# main.net
KiCad netlist of a schematic drawn in Altium Designer
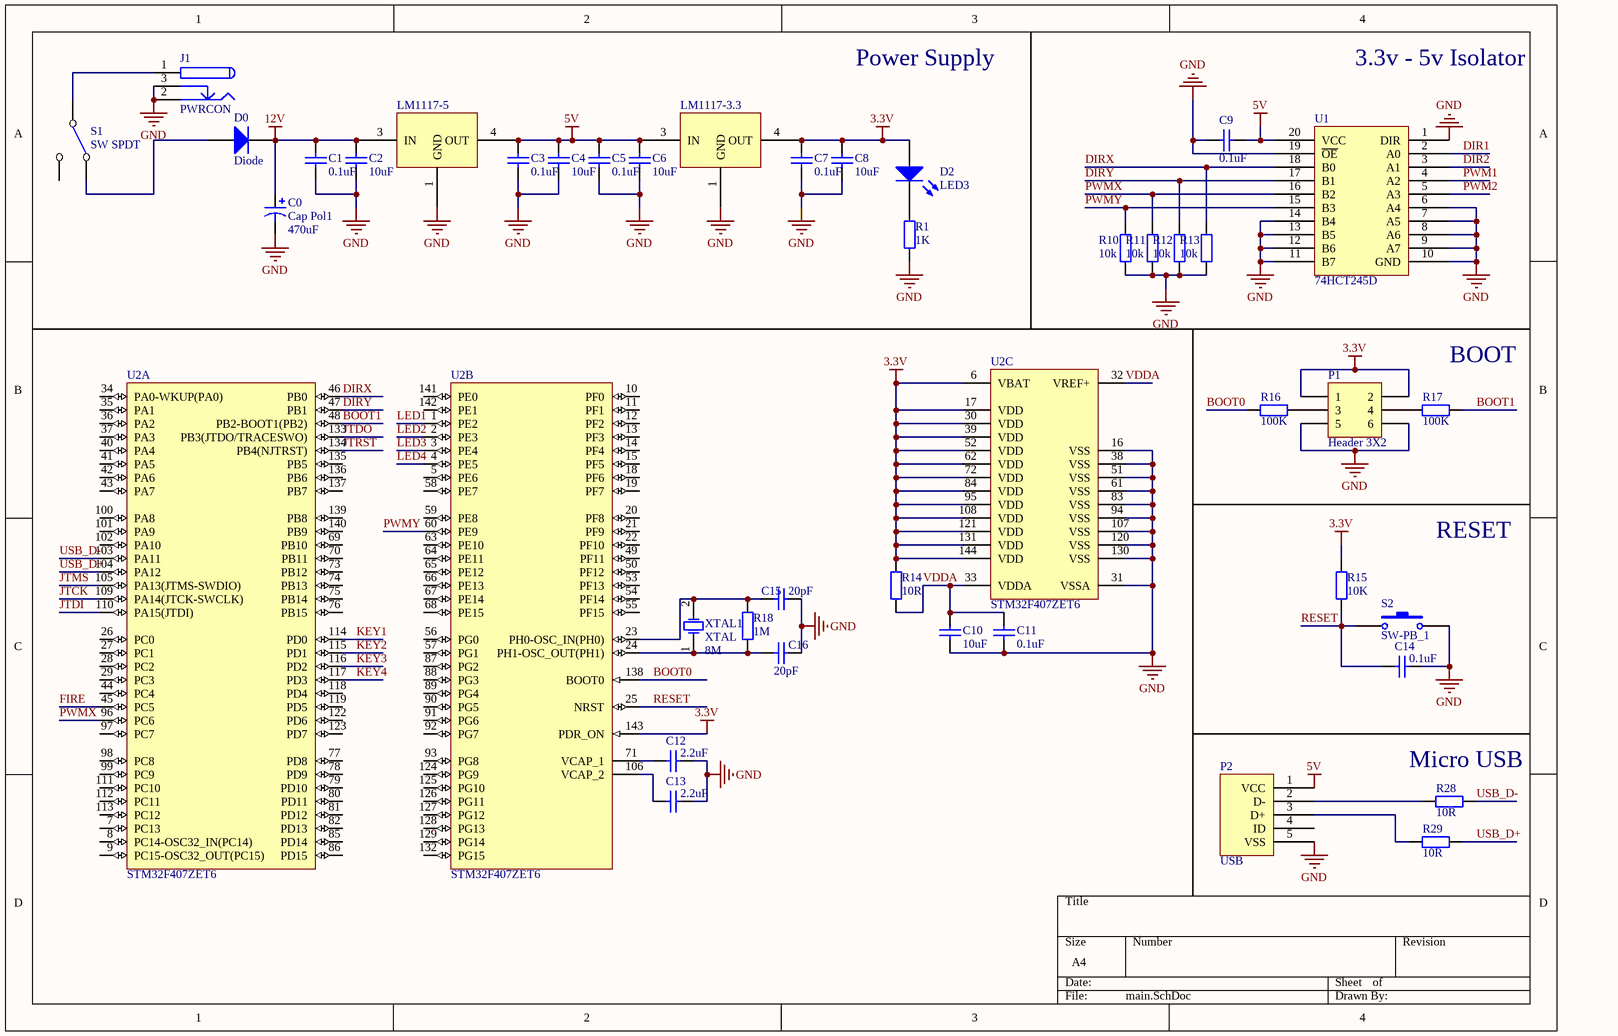
[diagram p0: main.SchDoc]

(export (version "E")
  (design (tool "Eeschema 10.0.6"))
  (components
    (comp (ref "C0")
      (value "Cap Pol1")
      (footprint "CAP-10")
      (description "Polarized Capacitor (Radial)")
      (fields (field (name "ALTIUM_VALUE") "470uF") (field (name "PUBLISHER") "Altium Limited"))
      (libsource (lib "Miscellaneous Devices") (part "Cap Pol1"))
    )
    (comp (ref "C1")
      (value "0.1uF")
      (footprint "C-0603")
      (description "Capacitor (Semiconductor SIM Model)")
      (fields (field (name "Comment") "Cap") (field (name "PUBLISHER") "Altium Limited"))
      (libsource (lib "Miscellaneous Devices") (part "Cap Semi"))
    )
    (comp (ref "C2")
      (value "10uF")
      (footprint "C-0603")
      (description "Capacitor (Semiconductor SIM Model)")
      (fields (field (name "Comment") "Cap") (field (name "PUBLISHER") "Altium Limited"))
      (libsource (lib "Miscellaneous Devices") (part "Cap Semi"))
    )
    (comp (ref "C3")
      (value "0.1uF")
      (footprint "C-0603")
      (description "Capacitor (Semiconductor SIM Model)")
      (fields (field (name "Comment") "Cap") (field (name "PUBLISHER") "Altium Limited"))
      (libsource (lib "Miscellaneous Devices") (part "Cap Semi"))
    )
    (comp (ref "C4")
      (value "10uF")
      (footprint "C-0603")
      (description "Capacitor (Semiconductor SIM Model)")
      (fields (field (name "Comment") "Cap") (field (name "PUBLISHER") "Altium Limited"))
      (libsource (lib "Miscellaneous Devices") (part "Cap Semi"))
    )
    (comp (ref "C5")
      (value "0.1uF")
      (footprint "C-0603")
      (description "Capacitor (Semiconductor SIM Model)")
      (fields (field (name "Comment") "Cap") (field (name "PUBLISHER") "Altium Limited"))
      (libsource (lib "Miscellaneous Devices") (part "Cap Semi"))
    )
    (comp (ref "C6")
      (value "10uF")
      (footprint "C-0603")
      (description "Capacitor (Semiconductor SIM Model)")
      (fields (field (name "Comment") "Cap") (field (name "PUBLISHER") "Altium Limited"))
      (libsource (lib "Miscellaneous Devices") (part "Cap Semi"))
    )
    (comp (ref "C7")
      (value "0.1uF")
      (footprint "C-0603")
      (description "Capacitor (Semiconductor SIM Model)")
      (fields (field (name "Comment") "Cap") (field (name "PUBLISHER") "Altium Limited"))
      (libsource (lib "Miscellaneous Devices") (part "Cap Semi"))
    )
    (comp (ref "C8")
      (value "10uF")
      (footprint "C-0603")
      (description "Capacitor (Semiconductor SIM Model)")
      (fields (field (name "Comment") "Cap") (field (name "PUBLISHER") "Altium Limited"))
      (libsource (lib "Miscellaneous Devices") (part "Cap Semi"))
    )
    (comp (ref "C9")
      (value "0.1uF")
      (footprint "C-0603")
      (description "Capacitor (Semiconductor SIM Model)")
      (fields (field (name "Comment") "Cap") (field (name "PUBLISHER") "Altium Limited"))
      (libsource (lib "Miscellaneous Devices") (part "Cap Semi"))
    )
    (comp (ref "C10")
      (value "10uF")
      (footprint "C-0603")
      (description "Capacitor (Semiconductor SIM Model)")
      (fields (field (name "Comment") "Cap") (field (name "PUBLISHER") "Altium Limited"))
      (libsource (lib "Miscellaneous Devices") (part "Cap Semi"))
    )
    (comp (ref "C11")
      (value "0.1uF")
      (footprint "C-0603")
      (description "Capacitor (Semiconductor SIM Model)")
      (fields (field (name "Comment") "Cap") (field (name "PUBLISHER") "Altium Limited"))
      (libsource (lib "Miscellaneous Devices") (part "Cap Semi"))
    )
    (comp (ref "C12")
      (value "2.2uF")
      (footprint "C-0603")
      (description "Capacitor (Semiconductor SIM Model)")
      (fields (field (name "Comment") "Cap") (field (name "PUBLISHER") "Altium Limited"))
      (libsource (lib "Miscellaneous Devices") (part "Cap Semi"))
    )
    (comp (ref "C13")
      (value "2.2uF")
      (footprint "C-0603")
      (description "Capacitor (Semiconductor SIM Model)")
      (fields (field (name "Comment") "Cap") (field (name "PUBLISHER") "Altium Limited"))
      (libsource (lib "Miscellaneous Devices") (part "Cap Semi"))
    )
    (comp (ref "C14")
      (value "0.1uF")
      (footprint "C-0603")
      (description "Capacitor (Semiconductor SIM Model)")
      (fields (field (name "Comment") "Cap") (field (name "PUBLISHER") "Altium Limited"))
      (libsource (lib "Miscellaneous Devices") (part "Cap Semi"))
    )
    (comp (ref "C15")
      (value "20pF")
      (footprint "C-0603")
      (description "Capacitor (Semiconductor SIM Model)")
      (fields (field (name "Comment") "Cap") (field (name "PUBLISHER") "Altium Limited"))
      (libsource (lib "Miscellaneous Devices") (part "Cap Semi"))
    )
    (comp (ref "C16")
      (value "20pF")
      (footprint "C-0603")
      (description "Capacitor (Semiconductor SIM Model)")
      (fields (field (name "Comment") "Cap") (field (name "PUBLISHER") "Altium Limited"))
      (libsource (lib "Miscellaneous Devices") (part "Cap Semi"))
    )
    (comp (ref "D0")
      (value "Diode")
      (footprint "DIODE-SMA/SMB")
      (description "Default Diode")
      (fields (field (name "PUBLISHER") "Altium Limited"))
      (libsource (lib "Miscellaneous Devices") (part "Diode"))
    )
    (comp (ref "D2")
      (value "LED3")
      (footprint "DIODE-1206")
      (description "Typical BLUE SiC LED")
      (fields (field (name "PUBLISHER") "Altium Limited"))
      (libsource (lib "Miscellaneous Devices") (part "LED3"))
    )
    (comp (ref "J1")
      (value "PWRCON")
      (footprint "DC-005A")
      (description "直流电源端子")
      (fields (field (name "PUBLISHER") "Altium Limited"))
      (libsource (lib "HDR_fszhang") (part "PWRCON"))
    )
    (comp (ref "LM1117-3.3") (value "LM1117") (footprint "lm1117") (libsource (lib "MOS_H") (part "LM1117")))
    (comp (ref "LM1117-5") (value "LM1117") (footprint "lm1117") (libsource (lib "MOS_H") (part "LM1117")))
    (comp (ref "P1")
      (value "Header 3X2")
      (footprint "HDR2X3")
      (description "Header, 3-Pin, Dual row")
      (fields (field (name "PUBLISHER") "Altium Limited"))
      (libsource (lib "Miscellaneous Connectors") (part "Header 3X2"))
    )
    (comp (ref "P2") (value "USB") (footprint "USB_MINI") (libsource (lib "mcu_board") (part "USB")))
    (comp (ref "R1")
      (value "1K")
      (footprint "R-0603")
      (description "Resistor")
      (fields (field (name "Comment") "Res2") (field (name "PUBLISHER") "Altium Limited"))
      (libsource (lib "") (part "Res2_3"))
    )
    (comp (ref "R10")
      (value "10k")
      (footprint "R-0603")
      (description "Resistor")
      (fields (field (name "Comment") "Res2") (field (name "PUBLISHER") "Altium Limited"))
      (libsource (lib "Miscellaneous Devices") (part "Res2"))
    )
    (comp (ref "R11")
      (value "10k")
      (footprint "R-0603")
      (description "Resistor")
      (fields (field (name "Comment") "Res2") (field (name "PUBLISHER") "Altium Limited"))
      (libsource (lib "Miscellaneous Devices") (part "Res2"))
    )
    (comp (ref "R12")
      (value "10k")
      (footprint "R-0603")
      (description "Resistor")
      (fields (field (name "Comment") "Res2") (field (name "PUBLISHER") "Altium Limited"))
      (libsource (lib "Miscellaneous Devices") (part "Res2"))
    )
    (comp (ref "R13")
      (value "10k")
      (footprint "R-0603")
      (description "Resistor")
      (fields (field (name "Comment") "Res2") (field (name "PUBLISHER") "Altium Limited"))
      (libsource (lib "Miscellaneous Devices") (part "Res2"))
    )
    (comp (ref "R14")
      (value "10R")
      (footprint "R-0603")
      (description "Resistor")
      (fields (field (name "Comment") "Res2") (field (name "PUBLISHER") "Altium Limited"))
      (libsource (lib "") (part "Res2_2"))
    )
    (comp (ref "R15")
      (value "10K")
      (footprint "R-0603")
      (description "Resistor")
      (fields (field (name "Comment") "Res2") (field (name "PUBLISHER") "Altium Limited"))
      (libsource (lib "") (part "Res2_2"))
    )
    (comp (ref "R16")
      (value "100K")
      (footprint "R-0603")
      (description "Resistor")
      (fields (field (name "Comment") "Res2") (field (name "PUBLISHER") "Altium Limited"))
      (libsource (lib "") (part "Res2_1"))
    )
    (comp (ref "R17")
      (value "100K")
      (footprint "R-0603")
      (description "Resistor")
      (fields (field (name "Comment") "Res2") (field (name "PUBLISHER") "Altium Limited"))
      (libsource (lib "") (part "Res2_1"))
    )
    (comp (ref "R18")
      (value "1M")
      (footprint "R-0603")
      (description "Resistor")
      (fields (field (name "Comment") "Res2") (field (name "PUBLISHER") "Altium Limited"))
      (libsource (lib "") (part "Res2_2"))
    )
    (comp (ref "R28")
      (value "10R")
      (footprint "R-0603")
      (description "Resistor")
      (fields (field (name "Comment") "Res2") (field (name "PUBLISHER") "Altium Limited"))
      (libsource (lib "") (part "Res2_1"))
    )
    (comp (ref "R29")
      (value "10R")
      (footprint "R-0603")
      (description "Resistor")
      (fields (field (name "Comment") "Res2") (field (name "PUBLISHER") "Altium Limited"))
      (libsource (lib "") (part "Res2_1"))
    )
    (comp (ref "S1") (value "SW SPDT") (footprint "SW3P") (libsource (lib "MOS_H") (part "SW SPDT")))
    (comp (ref "S2")
      (value "SW-PB_1")
      (footprint "SW-2-6*3")
      (description "Switch")
      (fields (field (name "PUBLISHER") "Altium Limited"))
      (libsource (lib "mcu_board") (part "SW-PB_1"))
    )
    (comp (ref "U1") (value "74HCT245D") (footprint "TSSOP20") (libsource (lib "MOS_H") (part "74lvc245")))
    (comp (ref "U2")
      (value "STM32F407ZET6")
      (footprint "STM-LQFP144_M")
      (fields (field (name "MANUFACTURER") "STMicroelectronics"))
      (libsource (lib "STMicroelectronics STM32 F4") (part "STM32F407ZET6"))
    )
    (comp (ref "XTAL1")
      (value "XTAL")
      (footprint "XTAL-QC49/SMD")
      (fields (field (name "FREQUENCE") "8M"))
      (libsource (lib "mcu_board") (part "XTAL"))
    )
  )
  (nets
    (net (code "1") (name "/BOOT0") (class "Default")
      (node (ref "R16") (pin "2") (pinfunction "2_2") (pintype "passive"))
      (node (ref "U2") (pin "138") (pinfunction "BOOT0_138") (pintype "input"))
    )
    (net (code "2") (name "/BOOT1") (class "Default")
      (node (ref "R17") (pin "1") (pinfunction "1_1") (pintype "passive"))
      (node (ref "U2") (pin "48") (pinfunction "PB2-BOOT1(PB2)_48") (pintype "bidirectional"))
    )
    (net (code "3") (name "/DIR1") (class "Default")
      (node (ref "U1") (pin "2") (pinfunction "A0_2") (pintype "passive"))
    )
    (net (code "4") (name "/DIR2") (class "Default")
      (node (ref "U1") (pin "3") (pinfunction "A1_3") (pintype "passive"))
    )
    (net (code "5") (name "/DIRX") (class "Default")
      (node (ref "R13") (pin "1") (pinfunction "1_1") (pintype "passive"))
      (node (ref "U1") (pin "18") (pinfunction "B0_18") (pintype "passive"))
      (node (ref "U2") (pin "46") (pinfunction "PB0_46") (pintype "bidirectional"))
    )
    (net (code "6") (name "/DIRY") (class "Default")
      (node (ref "R12") (pin "1") (pinfunction "1_1") (pintype "passive"))
      (node (ref "U1") (pin "17") (pinfunction "B1_17") (pintype "passive"))
      (node (ref "U2") (pin "47") (pinfunction "PB1_47") (pintype "bidirectional"))
    )
    (net (code "7") (name "/FIRE") (class "Default")
      (node (ref "U2") (pin "45") (pinfunction "PC5_45") (pintype "bidirectional"))
    )
    (net (code "8") (name "/JTCK") (class "Default")
      (node (ref "U2") (pin "109") (pinfunction "PA14(JTCK-SWCLK)_109") (pintype "bidirectional"))
    )
    (net (code "9") (name "/JTDI") (class "Default")
      (node (ref "U2") (pin "110") (pinfunction "PA15(JTDI)_110") (pintype "bidirectional"))
    )
    (net (code "10") (name "/JTDO") (class "Default")
      (node (ref "U2") (pin "133") (pinfunction "PB3(JTDO/TRACESWO)_133") (pintype "bidirectional"))
    )
    (net (code "11") (name "/JTMS") (class "Default")
      (node (ref "U2") (pin "105") (pinfunction "PA13(JTMS-SWDIO)_105") (pintype "bidirectional"))
    )
    (net (code "12") (name "/JTRST") (class "Default")
      (node (ref "U2") (pin "134") (pinfunction "PB4(NJTRST)_134") (pintype "bidirectional"))
    )
    (net (code "13") (name "/KEY1") (class "Default")
      (node (ref "U2") (pin "114") (pinfunction "PD0_114") (pintype "bidirectional"))
    )
    (net (code "14") (name "/KEY2") (class "Default")
      (node (ref "U2") (pin "115") (pinfunction "PD1_115") (pintype "bidirectional"))
    )
    (net (code "15") (name "/KEY3") (class "Default")
      (node (ref "U2") (pin "116") (pinfunction "PD2_116") (pintype "bidirectional"))
    )
    (net (code "16") (name "/KEY4") (class "Default")
      (node (ref "U2") (pin "117") (pinfunction "PD3_117") (pintype "bidirectional"))
    )
    (net (code "17") (name "/LED1") (class "Default")
      (node (ref "U2") (pin "1") (pinfunction "PE2_1") (pintype "bidirectional"))
    )
    (net (code "18") (name "/LED2") (class "Default")
      (node (ref "U2") (pin "2") (pinfunction "PE3_2") (pintype "bidirectional"))
    )
    (net (code "19") (name "/LED3") (class "Default")
      (node (ref "U2") (pin "3") (pinfunction "PE4_3") (pintype "bidirectional"))
    )
    (net (code "20") (name "/LED4") (class "Default")
      (node (ref "U2") (pin "4") (pinfunction "PE5_4") (pintype "bidirectional"))
    )
    (net (code "21") (name "/PWM1") (class "Default")
      (node (ref "U1") (pin "4") (pinfunction "A2_4") (pintype "passive"))
    )
    (net (code "22") (name "/PWM2") (class "Default")
      (node (ref "U1") (pin "5") (pinfunction "A3_5") (pintype "passive"))
    )
    (net (code "23") (name "/PWMX") (class "Default")
      (node (ref "R11") (pin "1") (pinfunction "1_1") (pintype "passive"))
      (node (ref "U1") (pin "16") (pinfunction "B2_16") (pintype "passive"))
      (node (ref "U2") (pin "96") (pinfunction "PC6_96") (pintype "bidirectional"))
    )
    (net (code "24") (name "/PWMY") (class "Default")
      (node (ref "R10") (pin "1") (pinfunction "1_1") (pintype "passive"))
      (node (ref "U1") (pin "15") (pinfunction "B3_15") (pintype "passive"))
      (node (ref "U2") (pin "60") (pinfunction "PE9_60") (pintype "bidirectional"))
    )
    (net (code "25") (name "/RESET") (class "Default")
      (node (ref "C14") (pin "2") (pinfunction "2_2") (pintype "passive"))
      (node (ref "R15") (pin "1") (pinfunction "1_1") (pintype "passive"))
      (node (ref "S2") (pin "1") (pinfunction "1_1") (pintype "passive"))
      (node (ref "U2") (pin "25") (pinfunction "NRST_25") (pintype "bidirectional"))
    )
    (net (code "26") (name "/USB_D+") (class "Default")
      (node (ref "R29") (pin "1") (pinfunction "1_1") (pintype "passive"))
      (node (ref "U2") (pin "104") (pinfunction "PA12_104") (pintype "bidirectional"))
    )
    (net (code "27") (name "/USB_D-") (class "Default")
      (node (ref "R28") (pin "1") (pinfunction "1_1") (pintype "passive"))
      (node (ref "U2") (pin "103") (pinfunction "PA11_103") (pintype "bidirectional"))
    )
    (net (code "28") (name "/VDDA") (class "Default")
      (node (ref "C10") (pin "2") (pinfunction "2_2") (pintype "passive"))
      (node (ref "C11") (pin "2") (pinfunction "2_2") (pintype "passive"))
      (node (ref "R14") (pin "1") (pinfunction "1_1") (pintype "passive"))
      (node (ref "U2") (pin "32") (pinfunction "VREF+_32") (pintype "power_in"))
      (node (ref "U2") (pin "33") (pinfunction "VDDA_33") (pintype "power_in"))
    )
    (net (code "29") (name "3.3V") (class "Default")
      (node (ref "C7") (pin "2") (pinfunction "2_2") (pintype "passive"))
      (node (ref "C8") (pin "2") (pinfunction "2_2") (pintype "passive"))
      (node (ref "D2") (pin "1") (pinfunction "A_1") (pintype "passive"))
      (node (ref "LM1117-3.3") (pin "4") (pinfunction "OUT_4") (pintype "passive"))
      (node (ref "P1") (pin "1") (pinfunction "1_1") (pintype "passive"))
      (node (ref "P1") (pin "2") (pinfunction "2_2") (pintype "passive"))
      (node (ref "R14") (pin "2") (pinfunction "2_2") (pintype "passive"))
      (node (ref "R15") (pin "2") (pinfunction "2_2") (pintype "passive"))
      (node (ref "U2") (pin "108") (pinfunction "VDD_108") (pintype "power_in"))
      (node (ref "U2") (pin "121") (pinfunction "VDD_121") (pintype "power_in"))
      (node (ref "U2") (pin "131") (pinfunction "VDD_131") (pintype "power_in"))
      (node (ref "U2") (pin "143") (pinfunction "PDR_ON_143") (pintype "input"))
      (node (ref "U2") (pin "144") (pinfunction "VDD_144") (pintype "power_in"))
      (node (ref "U2") (pin "17") (pinfunction "VDD_17") (pintype "power_in"))
      (node (ref "U2") (pin "30") (pinfunction "VDD_30") (pintype "power_in"))
      (node (ref "U2") (pin "39") (pinfunction "VDD_39") (pintype "power_in"))
      (node (ref "U2") (pin "52") (pinfunction "VDD_52") (pintype "power_in"))
      (node (ref "U2") (pin "6") (pinfunction "VBAT_6") (pintype "power_in"))
      (node (ref "U2") (pin "62") (pinfunction "VDD_62") (pintype "power_in"))
      (node (ref "U2") (pin "72") (pinfunction "VDD_72") (pintype "power_in"))
      (node (ref "U2") (pin "84") (pinfunction "VDD_84") (pintype "power_in"))
      (node (ref "U2") (pin "95") (pinfunction "VDD_95") (pintype "power_in"))
    )
    (net (code "30") (name "5V") (class "Default")
      (node (ref "C3") (pin "2") (pinfunction "2_2") (pintype "passive"))
      (node (ref "C4") (pin "2") (pinfunction "2_2") (pintype "passive"))
      (node (ref "C5") (pin "2") (pinfunction "2_2") (pintype "passive"))
      (node (ref "C6") (pin "2") (pinfunction "2_2") (pintype "passive"))
      (node (ref "C9") (pin "1") (pinfunction "1_1") (pintype "passive"))
      (node (ref "LM1117-3.3") (pin "3") (pinfunction "IN_3") (pintype "passive"))
      (node (ref "LM1117-5") (pin "4") (pinfunction "OUT_4") (pintype "passive"))
      (node (ref "P2") (pin "1") (pinfunction "VCC_1") (pintype "passive"))
      (node (ref "U1") (pin "20") (pinfunction "VCC_20") (pintype "passive"))
    )
    (net (code "31") (name "12V") (class "Default")
      (node (ref "C0") (pin "1") (pinfunction "1_1") (pintype "passive"))
      (node (ref "C1") (pin "2") (pinfunction "2_2") (pintype "passive"))
      (node (ref "C2") (pin "2") (pinfunction "2_2") (pintype "passive"))
      (node (ref "D0") (pin "2") (pinfunction "K_2") (pintype "passive"))
      (node (ref "LM1117-5") (pin "3") (pinfunction "IN_3") (pintype "passive"))
    )
    (net (code "32") (name "GND") (class "Default")
      (node (ref "C0") (pin "2") (pinfunction "2_2") (pintype "passive"))
      (node (ref "C1") (pin "1") (pinfunction "1_1") (pintype "passive"))
      (node (ref "C10") (pin "1") (pinfunction "1_1") (pintype "passive"))
      (node (ref "C11") (pin "1") (pinfunction "1_1") (pintype "passive"))
      (node (ref "C12") (pin "1") (pinfunction "1_1") (pintype "passive"))
      (node (ref "C13") (pin "1") (pinfunction "1_1") (pintype "passive"))
      (node (ref "C14") (pin "1") (pinfunction "1_1") (pintype "passive"))
      (node (ref "C15") (pin "2") (pinfunction "2_2") (pintype "passive"))
      (node (ref "C16") (pin "2") (pinfunction "2_2") (pintype "passive"))
      (node (ref "C2") (pin "1") (pinfunction "1_1") (pintype "passive"))
      (node (ref "C3") (pin "1") (pinfunction "1_1") (pintype "passive"))
      (node (ref "C4") (pin "1") (pinfunction "1_1") (pintype "passive"))
      (node (ref "C5") (pin "1") (pinfunction "1_1") (pintype "passive"))
      (node (ref "C6") (pin "1") (pinfunction "1_1") (pintype "passive"))
      (node (ref "C7") (pin "1") (pinfunction "1_1") (pintype "passive"))
      (node (ref "C8") (pin "1") (pinfunction "1_1") (pintype "passive"))
      (node (ref "C9") (pin "2") (pinfunction "2_2") (pintype "passive"))
      (node (ref "J1") (pin "2") (pinfunction "2_2") (pintype "power_in"))
      (node (ref "J1") (pin "3") (pinfunction "3_3") (pintype "power_in"))
      (node (ref "LM1117-3.3") (pin "1") (pinfunction "GND_1") (pintype "passive"))
      (node (ref "LM1117-5") (pin "1") (pinfunction "GND_1") (pintype "passive"))
      (node (ref "P1") (pin "5") (pinfunction "5_5") (pintype "passive"))
      (node (ref "P1") (pin "6") (pinfunction "6_6") (pintype "passive"))
      (node (ref "P2") (pin "5") (pinfunction "VSS_5") (pintype "passive"))
      (node (ref "R1") (pin "1") (pinfunction "1_1") (pintype "passive"))
      (node (ref "R10") (pin "2") (pinfunction "2_2") (pintype "passive"))
      (node (ref "R11") (pin "2") (pinfunction "2_2") (pintype "passive"))
      (node (ref "R12") (pin "2") (pinfunction "2_2") (pintype "passive"))
      (node (ref "R13") (pin "2") (pinfunction "2_2") (pintype "passive"))
      (node (ref "S2") (pin "2") (pinfunction "2_2") (pintype "passive"))
      (node (ref "U1") (pin "1") (pinfunction "DIR_1") (pintype "passive"))
      (node (ref "U1") (pin "10") (pinfunction "GND_10") (pintype "passive"))
      (node (ref "U1") (pin "11") (pinfunction "B7_11") (pintype "passive"))
      (node (ref "U1") (pin "12") (pinfunction "B6_12") (pintype "passive"))
      (node (ref "U1") (pin "13") (pinfunction "B5_13") (pintype "passive"))
      (node (ref "U1") (pin "14") (pinfunction "B4_14") (pintype "passive"))
      (node (ref "U1") (pin "19") (pinfunction "~{OE}_19") (pintype "passive"))
      (node (ref "U1") (pin "6") (pinfunction "A4_6") (pintype "passive"))
      (node (ref "U1") (pin "7") (pinfunction "A5_7") (pintype "passive"))
      (node (ref "U1") (pin "8") (pinfunction "A6_8") (pintype "passive"))
      (node (ref "U1") (pin "9") (pinfunction "A7_9") (pintype "passive"))
      (node (ref "U2") (pin "107") (pinfunction "VSS_107") (pintype "power_in"))
      (node (ref "U2") (pin "120") (pinfunction "VSS_120") (pintype "power_in"))
      (node (ref "U2") (pin "130") (pinfunction "VSS_130") (pintype "power_in"))
      (node (ref "U2") (pin "16") (pinfunction "VSS_16") (pintype "power_in"))
      (node (ref "U2") (pin "31") (pinfunction "VSSA_31") (pintype "power_in"))
      (node (ref "U2") (pin "38") (pinfunction "VSS_38") (pintype "power_in"))
      (node (ref "U2") (pin "51") (pinfunction "VSS_51") (pintype "power_in"))
      (node (ref "U2") (pin "61") (pinfunction "VSS_61") (pintype "power_in"))
      (node (ref "U2") (pin "83") (pinfunction "VSS_83") (pintype "power_in"))
      (node (ref "U2") (pin "94") (pinfunction "VSS_94") (pintype "power_in"))
    )
    (net (code "33") (name "Net-(D0-A)") (class "Default")
      (node (ref "D0") (pin "1") (pinfunction "A_1") (pintype "passive"))
      (node (ref "S1") (pin "2") (pinfunction "NC_2") (pintype "passive"))
    )
    (net (code "34") (name "Net-(D2-K)") (class "Default")
      (node (ref "D2") (pin "2") (pinfunction "K_2") (pintype "passive"))
      (node (ref "R1") (pin "2") (pinfunction "2_2") (pintype "passive"))
    )
    (net (code "35") (name "Net-(P1-Pad3)") (class "Default")
      (node (ref "P1") (pin "3") (pinfunction "3_3") (pintype "passive"))
      (node (ref "R16") (pin "1") (pinfunction "1_1") (pintype "passive"))
    )
    (net (code "36") (name "Net-(P1-Pad4)") (class "Default")
      (node (ref "P1") (pin "4") (pinfunction "4_4") (pintype "passive"))
      (node (ref "R17") (pin "2") (pinfunction "2_2") (pintype "passive"))
    )
    (net (code "37") (name "Net-(P2-D+)") (class "Default")
      (node (ref "P2") (pin "3") (pinfunction "D+_3") (pintype "passive"))
      (node (ref "R29") (pin "2") (pinfunction "2_2") (pintype "passive"))
    )
    (net (code "38") (name "Net-(P2-D-)") (class "Default")
      (node (ref "P2") (pin "2") (pinfunction "D-_2") (pintype "passive"))
      (node (ref "R28") (pin "2") (pinfunction "2_2") (pintype "passive"))
    )
    (net (code "39") (name "Net-(S1-COMMON)") (class "Default")
      (node (ref "J1") (pin "1") (pinfunction "1_1") (pintype "power_in"))
      (node (ref "S1") (pin "1") (pinfunction "COMMON_1") (pintype "passive"))
    )
    (net (code "40") (name "Net-(U2B-PH0-OSC_IN(PH0))") (class "Default")
      (node (ref "C15") (pin "1") (pinfunction "1_1") (pintype "passive"))
      (node (ref "R18") (pin "2") (pinfunction "2_2") (pintype "passive"))
      (node (ref "U2") (pin "23") (pinfunction "PH0-OSC_IN(PH0)_23") (pintype "bidirectional"))
      (node (ref "XTAL1") (pin "2") (pinfunction "2_2") (pintype "passive"))
    )
    (net (code "41") (name "Net-(U2B-PH1-OSC_OUT(PH1))") (class "Default")
      (node (ref "C16") (pin "1") (pinfunction "1_1") (pintype "passive"))
      (node (ref "R18") (pin "1") (pinfunction "1_1") (pintype "passive"))
      (node (ref "U2") (pin "24") (pinfunction "PH1-OSC_OUT(PH1)_24") (pintype "bidirectional"))
      (node (ref "XTAL1") (pin "1") (pinfunction "1_1") (pintype "passive"))
    )
    (net (code "42") (name "Net-(U2B-VCAP_1)") (class "Default")
      (node (ref "C12") (pin "2") (pinfunction "2_2") (pintype "passive"))
      (node (ref "U2") (pin "71") (pinfunction "VCAP_1_71") (pintype "power_in"))
    )
    (net (code "43") (name "Net-(U2B-VCAP_2)") (class "Default")
      (node (ref "C13") (pin "2") (pinfunction "2_2") (pintype "passive"))
      (node (ref "U2") (pin "106") (pinfunction "VCAP_2_106") (pintype "power_in"))
    )
    (net (code "44") (name "unconnected-(P2-ID-Pad4)") (class "Default")
      (node (ref "P2") (pin "4") (pinfunction "ID_4") (pintype "passive"))
    )
    (net (code "45") (name "unconnected-(S1-NO-Pad3)") (class "Default")
      (node (ref "S1") (pin "3") (pinfunction "NO_3") (pintype "passive"))
    )
    (net (code "46") (name "unconnected-(U2A-PA0-WKUP(PA0)-Pad34)") (class "Default")
      (node (ref "U2") (pin "34") (pinfunction "PA0-WKUP(PA0)_34") (pintype "bidirectional"))
    )
    (net (code "47") (name "unconnected-(U2A-PA1-Pad35)") (class "Default")
      (node (ref "U2") (pin "35") (pinfunction "PA1_35") (pintype "bidirectional"))
    )
    (net (code "48") (name "unconnected-(U2A-PA2-Pad36)") (class "Default")
      (node (ref "U2") (pin "36") (pinfunction "PA2_36") (pintype "bidirectional"))
    )
    (net (code "49") (name "unconnected-(U2A-PA3-Pad37)") (class "Default")
      (node (ref "U2") (pin "37") (pinfunction "PA3_37") (pintype "bidirectional"))
    )
    (net (code "50") (name "unconnected-(U2A-PA4-Pad40)") (class "Default")
      (node (ref "U2") (pin "40") (pinfunction "PA4_40") (pintype "bidirectional"))
    )
    (net (code "51") (name "unconnected-(U2A-PA5-Pad41)") (class "Default")
      (node (ref "U2") (pin "41") (pinfunction "PA5_41") (pintype "bidirectional"))
    )
    (net (code "52") (name "unconnected-(U2A-PA6-Pad42)") (class "Default")
      (node (ref "U2") (pin "42") (pinfunction "PA6_42") (pintype "bidirectional"))
    )
    (net (code "53") (name "unconnected-(U2A-PA7-Pad43)") (class "Default")
      (node (ref "U2") (pin "43") (pinfunction "PA7_43") (pintype "bidirectional"))
    )
    (net (code "54") (name "unconnected-(U2A-PA8-Pad100)") (class "Default")
      (node (ref "U2") (pin "100") (pinfunction "PA8_100") (pintype "bidirectional"))
    )
    (net (code "55") (name "unconnected-(U2A-PA9-Pad101)") (class "Default")
      (node (ref "U2") (pin "101") (pinfunction "PA9_101") (pintype "bidirectional"))
    )
    (net (code "56") (name "unconnected-(U2A-PA10-Pad102)") (class "Default")
      (node (ref "U2") (pin "102") (pinfunction "PA10_102") (pintype "bidirectional"))
    )
    (net (code "57") (name "unconnected-(U2A-PB5-Pad135)") (class "Default")
      (node (ref "U2") (pin "135") (pinfunction "PB5_135") (pintype "bidirectional"))
    )
    (net (code "58") (name "unconnected-(U2A-PB6-Pad136)") (class "Default")
      (node (ref "U2") (pin "136") (pinfunction "PB6_136") (pintype "bidirectional"))
    )
    (net (code "59") (name "unconnected-(U2A-PB7-Pad137)") (class "Default")
      (node (ref "U2") (pin "137") (pinfunction "PB7_137") (pintype "bidirectional"))
    )
    (net (code "60") (name "unconnected-(U2A-PB8-Pad139)") (class "Default")
      (node (ref "U2") (pin "139") (pinfunction "PB8_139") (pintype "bidirectional"))
    )
    (net (code "61") (name "unconnected-(U2A-PB9-Pad140)") (class "Default")
      (node (ref "U2") (pin "140") (pinfunction "PB9_140") (pintype "bidirectional"))
    )
    (net (code "62") (name "unconnected-(U2A-PB10-Pad69)") (class "Default")
      (node (ref "U2") (pin "69") (pinfunction "PB10_69") (pintype "bidirectional"))
    )
    (net (code "63") (name "unconnected-(U2A-PB11-Pad70)") (class "Default")
      (node (ref "U2") (pin "70") (pinfunction "PB11_70") (pintype "bidirectional"))
    )
    (net (code "64") (name "unconnected-(U2A-PB12-Pad73)") (class "Default")
      (node (ref "U2") (pin "73") (pinfunction "PB12_73") (pintype "bidirectional"))
    )
    (net (code "65") (name "unconnected-(U2A-PB13-Pad74)") (class "Default")
      (node (ref "U2") (pin "74") (pinfunction "PB13_74") (pintype "bidirectional"))
    )
    (net (code "66") (name "unconnected-(U2A-PB14-Pad75)") (class "Default")
      (node (ref "U2") (pin "75") (pinfunction "PB14_75") (pintype "bidirectional"))
    )
    (net (code "67") (name "unconnected-(U2A-PB15-Pad76)") (class "Default")
      (node (ref "U2") (pin "76") (pinfunction "PB15_76") (pintype "bidirectional"))
    )
    (net (code "68") (name "unconnected-(U2A-PC0-Pad26)") (class "Default")
      (node (ref "U2") (pin "26") (pinfunction "PC0_26") (pintype "bidirectional"))
    )
    (net (code "69") (name "unconnected-(U2A-PC1-Pad27)") (class "Default")
      (node (ref "U2") (pin "27") (pinfunction "PC1_27") (pintype "bidirectional"))
    )
    (net (code "70") (name "unconnected-(U2A-PC2-Pad28)") (class "Default")
      (node (ref "U2") (pin "28") (pinfunction "PC2_28") (pintype "bidirectional"))
    )
    (net (code "71") (name "unconnected-(U2A-PC3-Pad29)") (class "Default")
      (node (ref "U2") (pin "29") (pinfunction "PC3_29") (pintype "bidirectional"))
    )
    (net (code "72") (name "unconnected-(U2A-PC4-Pad44)") (class "Default")
      (node (ref "U2") (pin "44") (pinfunction "PC4_44") (pintype "bidirectional"))
    )
    (net (code "73") (name "unconnected-(U2A-PC7-Pad97)") (class "Default")
      (node (ref "U2") (pin "97") (pinfunction "PC7_97") (pintype "bidirectional"))
    )
    (net (code "74") (name "unconnected-(U2A-PC8-Pad98)") (class "Default")
      (node (ref "U2") (pin "98") (pinfunction "PC8_98") (pintype "bidirectional"))
    )
    (net (code "75") (name "unconnected-(U2A-PC9-Pad99)") (class "Default")
      (node (ref "U2") (pin "99") (pinfunction "PC9_99") (pintype "bidirectional"))
    )
    (net (code "76") (name "unconnected-(U2A-PC10-Pad111)") (class "Default")
      (node (ref "U2") (pin "111") (pinfunction "PC10_111") (pintype "bidirectional"))
    )
    (net (code "77") (name "unconnected-(U2A-PC11-Pad112)") (class "Default")
      (node (ref "U2") (pin "112") (pinfunction "PC11_112") (pintype "bidirectional"))
    )
    (net (code "78") (name "unconnected-(U2A-PC12-Pad113)") (class "Default")
      (node (ref "U2") (pin "113") (pinfunction "PC12_113") (pintype "bidirectional"))
    )
    (net (code "79") (name "unconnected-(U2A-PC13-Pad7)") (class "Default")
      (node (ref "U2") (pin "7") (pinfunction "PC13_7") (pintype "bidirectional"))
    )
    (net (code "80") (name "unconnected-(U2A-PC14-OSC32_IN(PC14)-Pad8)") (class "Default")
      (node (ref "U2") (pin "8") (pinfunction "PC14-OSC32_IN(PC14)_8") (pintype "bidirectional"))
    )
    (net (code "81") (name "unconnected-(U2A-PC15-OSC32_OUT(PC15)-Pad9)") (class "Default")
      (node (ref "U2") (pin "9") (pinfunction "PC15-OSC32_OUT(PC15)_9") (pintype "bidirectional"))
    )
    (net (code "82") (name "unconnected-(U2A-PD4-Pad118)") (class "Default")
      (node (ref "U2") (pin "118") (pinfunction "PD4_118") (pintype "bidirectional"))
    )
    (net (code "83") (name "unconnected-(U2A-PD5-Pad119)") (class "Default")
      (node (ref "U2") (pin "119") (pinfunction "PD5_119") (pintype "bidirectional"))
    )
    (net (code "84") (name "unconnected-(U2A-PD6-Pad122)") (class "Default")
      (node (ref "U2") (pin "122") (pinfunction "PD6_122") (pintype "bidirectional"))
    )
    (net (code "85") (name "unconnected-(U2A-PD7-Pad123)") (class "Default")
      (node (ref "U2") (pin "123") (pinfunction "PD7_123") (pintype "bidirectional"))
    )
    (net (code "86") (name "unconnected-(U2A-PD8-Pad77)") (class "Default")
      (node (ref "U2") (pin "77") (pinfunction "PD8_77") (pintype "bidirectional"))
    )
    (net (code "87") (name "unconnected-(U2A-PD9-Pad78)") (class "Default")
      (node (ref "U2") (pin "78") (pinfunction "PD9_78") (pintype "bidirectional"))
    )
    (net (code "88") (name "unconnected-(U2A-PD10-Pad79)") (class "Default")
      (node (ref "U2") (pin "79") (pinfunction "PD10_79") (pintype "bidirectional"))
    )
    (net (code "89") (name "unconnected-(U2A-PD11-Pad80)") (class "Default")
      (node (ref "U2") (pin "80") (pinfunction "PD11_80") (pintype "bidirectional"))
    )
    (net (code "90") (name "unconnected-(U2A-PD12-Pad81)") (class "Default")
      (node (ref "U2") (pin "81") (pinfunction "PD12_81") (pintype "bidirectional"))
    )
    (net (code "91") (name "unconnected-(U2A-PD13-Pad82)") (class "Default")
      (node (ref "U2") (pin "82") (pinfunction "PD13_82") (pintype "bidirectional"))
    )
    (net (code "92") (name "unconnected-(U2A-PD14-Pad85)") (class "Default")
      (node (ref "U2") (pin "85") (pinfunction "PD14_85") (pintype "bidirectional"))
    )
    (net (code "93") (name "unconnected-(U2A-PD15-Pad86)") (class "Default")
      (node (ref "U2") (pin "86") (pinfunction "PD15_86") (pintype "bidirectional"))
    )
    (net (code "94") (name "unconnected-(U2B-PE0-Pad141)") (class "Default")
      (node (ref "U2") (pin "141") (pinfunction "PE0_141") (pintype "bidirectional"))
    )
    (net (code "95") (name "unconnected-(U2B-PE1-Pad142)") (class "Default")
      (node (ref "U2") (pin "142") (pinfunction "PE1_142") (pintype "bidirectional"))
    )
    (net (code "96") (name "unconnected-(U2B-PE6-Pad5)") (class "Default")
      (node (ref "U2") (pin "5") (pinfunction "PE6_5") (pintype "bidirectional"))
    )
    (net (code "97") (name "unconnected-(U2B-PE7-Pad58)") (class "Default")
      (node (ref "U2") (pin "58") (pinfunction "PE7_58") (pintype "bidirectional"))
    )
    (net (code "98") (name "unconnected-(U2B-PE8-Pad59)") (class "Default")
      (node (ref "U2") (pin "59") (pinfunction "PE8_59") (pintype "bidirectional"))
    )
    (net (code "99") (name "unconnected-(U2B-PE10-Pad63)") (class "Default")
      (node (ref "U2") (pin "63") (pinfunction "PE10_63") (pintype "bidirectional"))
    )
    (net (code "100") (name "unconnected-(U2B-PE11-Pad64)") (class "Default")
      (node (ref "U2") (pin "64") (pinfunction "PE11_64") (pintype "bidirectional"))
    )
    (net (code "101") (name "unconnected-(U2B-PE12-Pad65)") (class "Default")
      (node (ref "U2") (pin "65") (pinfunction "PE12_65") (pintype "bidirectional"))
    )
    (net (code "102") (name "unconnected-(U2B-PE13-Pad66)") (class "Default")
      (node (ref "U2") (pin "66") (pinfunction "PE13_66") (pintype "bidirectional"))
    )
    (net (code "103") (name "unconnected-(U2B-PE14-Pad67)") (class "Default")
      (node (ref "U2") (pin "67") (pinfunction "PE14_67") (pintype "bidirectional"))
    )
    (net (code "104") (name "unconnected-(U2B-PE15-Pad68)") (class "Default")
      (node (ref "U2") (pin "68") (pinfunction "PE15_68") (pintype "bidirectional"))
    )
    (net (code "105") (name "unconnected-(U2B-PF0-Pad10)") (class "Default")
      (node (ref "U2") (pin "10") (pinfunction "PF0_10") (pintype "bidirectional"))
    )
    (net (code "106") (name "unconnected-(U2B-PF1-Pad11)") (class "Default")
      (node (ref "U2") (pin "11") (pinfunction "PF1_11") (pintype "bidirectional"))
    )
    (net (code "107") (name "unconnected-(U2B-PF2-Pad12)") (class "Default")
      (node (ref "U2") (pin "12") (pinfunction "PF2_12") (pintype "bidirectional"))
    )
    (net (code "108") (name "unconnected-(U2B-PF3-Pad13)") (class "Default")
      (node (ref "U2") (pin "13") (pinfunction "PF3_13") (pintype "bidirectional"))
    )
    (net (code "109") (name "unconnected-(U2B-PF4-Pad14)") (class "Default")
      (node (ref "U2") (pin "14") (pinfunction "PF4_14") (pintype "bidirectional"))
    )
    (net (code "110") (name "unconnected-(U2B-PF5-Pad15)") (class "Default")
      (node (ref "U2") (pin "15") (pinfunction "PF5_15") (pintype "bidirectional"))
    )
    (net (code "111") (name "unconnected-(U2B-PF6-Pad18)") (class "Default")
      (node (ref "U2") (pin "18") (pinfunction "PF6_18") (pintype "bidirectional"))
    )
    (net (code "112") (name "unconnected-(U2B-PF7-Pad19)") (class "Default")
      (node (ref "U2") (pin "19") (pinfunction "PF7_19") (pintype "bidirectional"))
    )
    (net (code "113") (name "unconnected-(U2B-PF8-Pad20)") (class "Default")
      (node (ref "U2") (pin "20") (pinfunction "PF8_20") (pintype "bidirectional"))
    )
    (net (code "114") (name "unconnected-(U2B-PF9-Pad21)") (class "Default")
      (node (ref "U2") (pin "21") (pinfunction "PF9_21") (pintype "bidirectional"))
    )
    (net (code "115") (name "unconnected-(U2B-PF10-Pad22)") (class "Default")
      (node (ref "U2") (pin "22") (pinfunction "PF10_22") (pintype "bidirectional"))
    )
    (net (code "116") (name "unconnected-(U2B-PF11-Pad49)") (class "Default")
      (node (ref "U2") (pin "49") (pinfunction "PF11_49") (pintype "bidirectional"))
    )
    (net (code "117") (name "unconnected-(U2B-PF12-Pad50)") (class "Default")
      (node (ref "U2") (pin "50") (pinfunction "PF12_50") (pintype "bidirectional"))
    )
    (net (code "118") (name "unconnected-(U2B-PF13-Pad53)") (class "Default")
      (node (ref "U2") (pin "53") (pinfunction "PF13_53") (pintype "bidirectional"))
    )
    (net (code "119") (name "unconnected-(U2B-PF14-Pad54)") (class "Default")
      (node (ref "U2") (pin "54") (pinfunction "PF14_54") (pintype "bidirectional"))
    )
    (net (code "120") (name "unconnected-(U2B-PF15-Pad55)") (class "Default")
      (node (ref "U2") (pin "55") (pinfunction "PF15_55") (pintype "bidirectional"))
    )
    (net (code "121") (name "unconnected-(U2B-PG0-Pad56)") (class "Default")
      (node (ref "U2") (pin "56") (pinfunction "PG0_56") (pintype "bidirectional"))
    )
    (net (code "122") (name "unconnected-(U2B-PG1-Pad57)") (class "Default")
      (node (ref "U2") (pin "57") (pinfunction "PG1_57") (pintype "bidirectional"))
    )
    (net (code "123") (name "unconnected-(U2B-PG2-Pad87)") (class "Default")
      (node (ref "U2") (pin "87") (pinfunction "PG2_87") (pintype "bidirectional"))
    )
    (net (code "124") (name "unconnected-(U2B-PG3-Pad88)") (class "Default")
      (node (ref "U2") (pin "88") (pinfunction "PG3_88") (pintype "bidirectional"))
    )
    (net (code "125") (name "unconnected-(U2B-PG4-Pad89)") (class "Default")
      (node (ref "U2") (pin "89") (pinfunction "PG4_89") (pintype "bidirectional"))
    )
    (net (code "126") (name "unconnected-(U2B-PG5-Pad90)") (class "Default")
      (node (ref "U2") (pin "90") (pinfunction "PG5_90") (pintype "bidirectional"))
    )
    (net (code "127") (name "unconnected-(U2B-PG6-Pad91)") (class "Default")
      (node (ref "U2") (pin "91") (pinfunction "PG6_91") (pintype "bidirectional"))
    )
    (net (code "128") (name "unconnected-(U2B-PG7-Pad92)") (class "Default")
      (node (ref "U2") (pin "92") (pinfunction "PG7_92") (pintype "bidirectional"))
    )
    (net (code "129") (name "unconnected-(U2B-PG8-Pad93)") (class "Default")
      (node (ref "U2") (pin "93") (pinfunction "PG8_93") (pintype "bidirectional"))
    )
    (net (code "130") (name "unconnected-(U2B-PG9-Pad124)") (class "Default")
      (node (ref "U2") (pin "124") (pinfunction "PG9_124") (pintype "bidirectional"))
    )
    (net (code "131") (name "unconnected-(U2B-PG10-Pad125)") (class "Default")
      (node (ref "U2") (pin "125") (pinfunction "PG10_125") (pintype "bidirectional"))
    )
    (net (code "132") (name "unconnected-(U2B-PG11-Pad126)") (class "Default")
      (node (ref "U2") (pin "126") (pinfunction "PG11_126") (pintype "bidirectional"))
    )
    (net (code "133") (name "unconnected-(U2B-PG12-Pad127)") (class "Default")
      (node (ref "U2") (pin "127") (pinfunction "PG12_127") (pintype "bidirectional"))
    )
    (net (code "134") (name "unconnected-(U2B-PG13-Pad128)") (class "Default")
      (node (ref "U2") (pin "128") (pinfunction "PG13_128") (pintype "bidirectional"))
    )
    (net (code "135") (name "unconnected-(U2B-PG14-Pad129)") (class "Default")
      (node (ref "U2") (pin "129") (pinfunction "PG14_129") (pintype "bidirectional"))
    )
    (net (code "136") (name "unconnected-(U2B-PG15-Pad132)") (class "Default")
      (node (ref "U2") (pin "132") (pinfunction "PG15_132") (pintype "bidirectional"))
    )
  )
)
